# Test.net
KiCad netlist of a schematic drawn in EAGLE
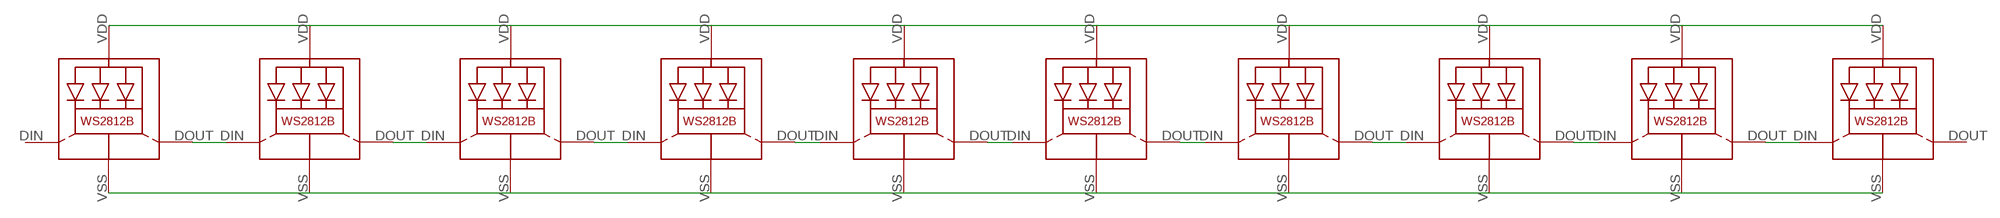
[diagram p0: schematic, sheet 1]

(export (version "E")
  (design (tool "Eeschema 10.0.6"))
  (components
    (comp (ref "LED1")
      (value "WS2812B")
      (footprint "eagle-import:WS2812B")
      (libsource (lib "eagle-import") (part "WS2812B"))
    )
    (comp (ref "LED2")
      (value "WS2812B")
      (footprint "eagle-import:WS2812B")
      (libsource (lib "eagle-import") (part "WS2812B"))
    )
    (comp (ref "LED3")
      (value "WS2812B")
      (footprint "eagle-import:WS2812B")
      (libsource (lib "eagle-import") (part "WS2812B"))
    )
    (comp (ref "LED4")
      (value "WS2812B")
      (footprint "eagle-import:WS2812B")
      (libsource (lib "eagle-import") (part "WS2812B"))
    )
    (comp (ref "LED5")
      (value "WS2812B")
      (footprint "eagle-import:WS2812B")
      (libsource (lib "eagle-import") (part "WS2812B"))
    )
    (comp (ref "LED6")
      (value "WS2812B")
      (footprint "eagle-import:WS2812B")
      (libsource (lib "eagle-import") (part "WS2812B"))
    )
    (comp (ref "LED7")
      (value "WS2812B")
      (footprint "eagle-import:WS2812B")
      (libsource (lib "eagle-import") (part "WS2812B"))
    )
    (comp (ref "LED8")
      (value "WS2812B")
      (footprint "eagle-import:WS2812B")
      (libsource (lib "eagle-import") (part "WS2812B"))
    )
    (comp (ref "LED9")
      (value "WS2812B")
      (footprint "eagle-import:WS2812B")
      (libsource (lib "eagle-import") (part "WS2812B"))
    )
    (comp (ref "LED10")
      (value "WS2812B")
      (footprint "eagle-import:WS2812B")
      (libsource (lib "eagle-import") (part "WS2812B"))
    )
  )
  (nets
    (net (code "1") (name "Net-(LED1-DO)") (class "Default")
      (node (ref "LED1") (pin "DOUT") (pinfunction "DO_DOUT") (pintype "output"))
      (node (ref "LED2") (pin "DIN") (pinfunction "DI_DIN") (pintype "input"))
    )
    (net (code "2") (name "Net-(LED1-GND)") (class "Default")
      (node (ref "LED1") (pin "VSS") (pinfunction "GND_VSS") (pintype "power_in"))
      (node (ref "LED10") (pin "VSS") (pinfunction "GND_VSS") (pintype "power_in"))
      (node (ref "LED2") (pin "VSS") (pinfunction "GND_VSS") (pintype "power_in"))
      (node (ref "LED3") (pin "VSS") (pinfunction "GND_VSS") (pintype "power_in"))
      (node (ref "LED4") (pin "VSS") (pinfunction "GND_VSS") (pintype "power_in"))
      (node (ref "LED5") (pin "VSS") (pinfunction "GND_VSS") (pintype "power_in"))
      (node (ref "LED6") (pin "VSS") (pinfunction "GND_VSS") (pintype "power_in"))
      (node (ref "LED7") (pin "VSS") (pinfunction "GND_VSS") (pintype "power_in"))
      (node (ref "LED8") (pin "VSS") (pinfunction "GND_VSS") (pintype "power_in"))
      (node (ref "LED9") (pin "VSS") (pinfunction "GND_VSS") (pintype "power_in"))
    )
    (net (code "3") (name "Net-(LED1-PadVDD)") (class "Default")
      (node (ref "LED1") (pin "VDD") (pinfunction "VDD_VDD") (pintype "power_in"))
      (node (ref "LED10") (pin "VDD") (pinfunction "VDD_VDD") (pintype "power_in"))
      (node (ref "LED2") (pin "VDD") (pinfunction "VDD_VDD") (pintype "power_in"))
      (node (ref "LED3") (pin "VDD") (pinfunction "VDD_VDD") (pintype "power_in"))
      (node (ref "LED4") (pin "VDD") (pinfunction "VDD_VDD") (pintype "power_in"))
      (node (ref "LED5") (pin "VDD") (pinfunction "VDD_VDD") (pintype "power_in"))
      (node (ref "LED6") (pin "VDD") (pinfunction "VDD_VDD") (pintype "power_in"))
      (node (ref "LED7") (pin "VDD") (pinfunction "VDD_VDD") (pintype "power_in"))
      (node (ref "LED8") (pin "VDD") (pinfunction "VDD_VDD") (pintype "power_in"))
      (node (ref "LED9") (pin "VDD") (pinfunction "VDD_VDD") (pintype "power_in"))
    )
    (net (code "4") (name "Net-(LED2-DO)") (class "Default")
      (node (ref "LED2") (pin "DOUT") (pinfunction "DO_DOUT") (pintype "output"))
      (node (ref "LED3") (pin "DIN") (pinfunction "DI_DIN") (pintype "input"))
    )
    (net (code "5") (name "Net-(LED3-DO)") (class "Default")
      (node (ref "LED3") (pin "DOUT") (pinfunction "DO_DOUT") (pintype "output"))
      (node (ref "LED4") (pin "DIN") (pinfunction "DI_DIN") (pintype "input"))
    )
    (net (code "6") (name "Net-(LED4-DO)") (class "Default")
      (node (ref "LED4") (pin "DOUT") (pinfunction "DO_DOUT") (pintype "output"))
      (node (ref "LED5") (pin "DIN") (pinfunction "DI_DIN") (pintype "input"))
    )
    (net (code "7") (name "Net-(LED5-DO)") (class "Default")
      (node (ref "LED5") (pin "DOUT") (pinfunction "DO_DOUT") (pintype "output"))
      (node (ref "LED6") (pin "DIN") (pinfunction "DI_DIN") (pintype "input"))
    )
    (net (code "8") (name "Net-(LED6-DO)") (class "Default")
      (node (ref "LED6") (pin "DOUT") (pinfunction "DO_DOUT") (pintype "output"))
      (node (ref "LED7") (pin "DIN") (pinfunction "DI_DIN") (pintype "input"))
    )
    (net (code "9") (name "Net-(LED7-DO)") (class "Default")
      (node (ref "LED7") (pin "DOUT") (pinfunction "DO_DOUT") (pintype "output"))
      (node (ref "LED8") (pin "DIN") (pinfunction "DI_DIN") (pintype "input"))
    )
    (net (code "10") (name "Net-(LED8-DO)") (class "Default")
      (node (ref "LED8") (pin "DOUT") (pinfunction "DO_DOUT") (pintype "output"))
      (node (ref "LED9") (pin "DIN") (pinfunction "DI_DIN") (pintype "input"))
    )
    (net (code "11") (name "Net-(LED10-DI)") (class "Default")
      (node (ref "LED10") (pin "DIN") (pinfunction "DI_DIN") (pintype "input"))
      (node (ref "LED9") (pin "DOUT") (pinfunction "DO_DOUT") (pintype "output"))
    )
    (net (code "12") (name "unconnected-(LED1-DI-PadDIN)") (class "Default")
      (node (ref "LED1") (pin "DIN") (pinfunction "DI_DIN") (pintype "input"))
    )
    (net (code "13") (name "unconnected-(LED10-DO-PadDOUT)") (class "Default")
      (node (ref "LED10") (pin "DOUT") (pinfunction "DO_DOUT") (pintype "output"))
    )
  )
)
